# HRD_2016.net
KiCad netlist of a schematic drawn in EAGLE
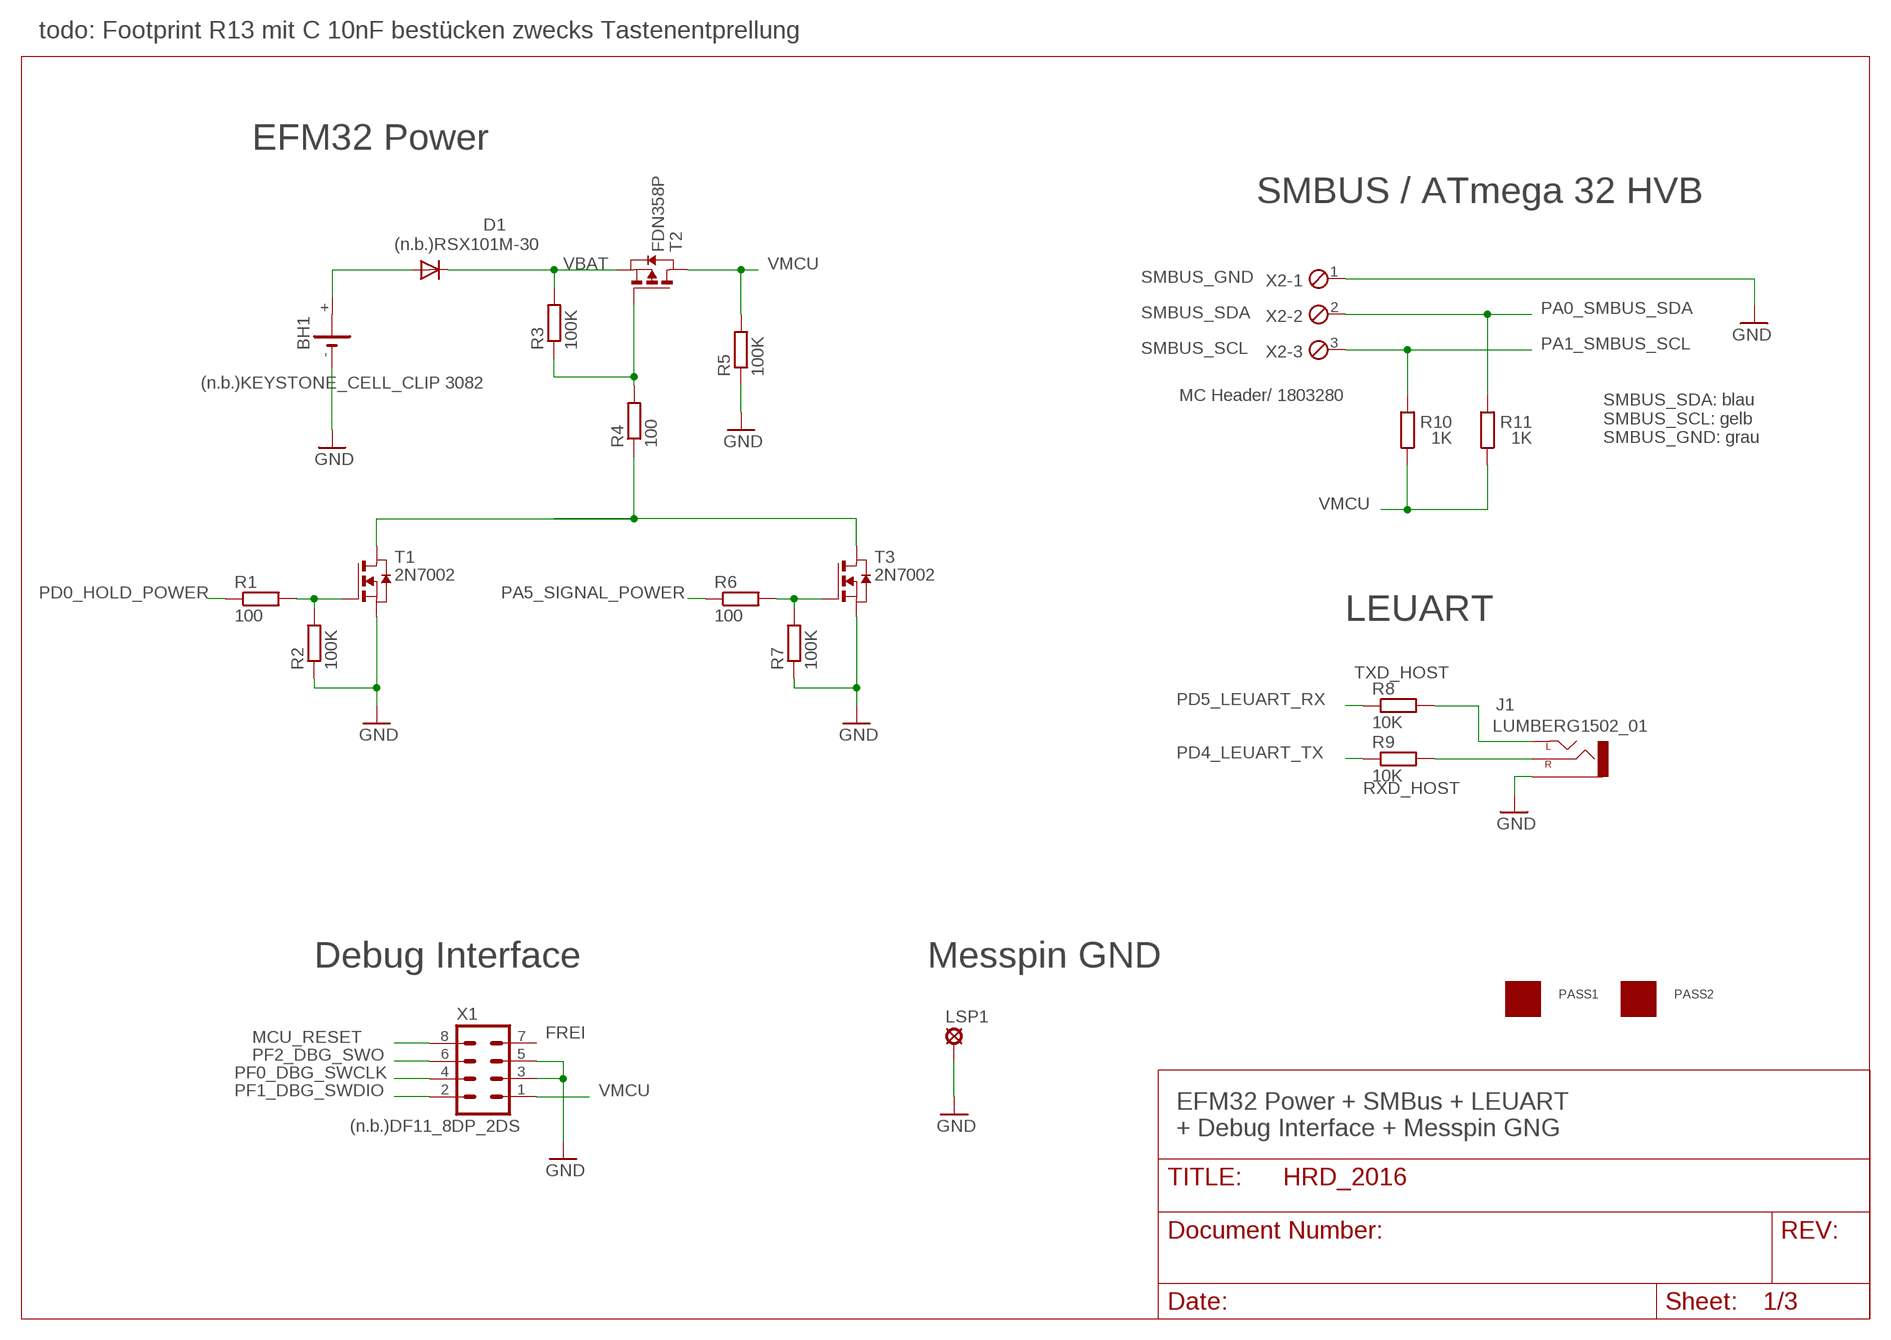
[diagram p0: schematic, sheet 1]
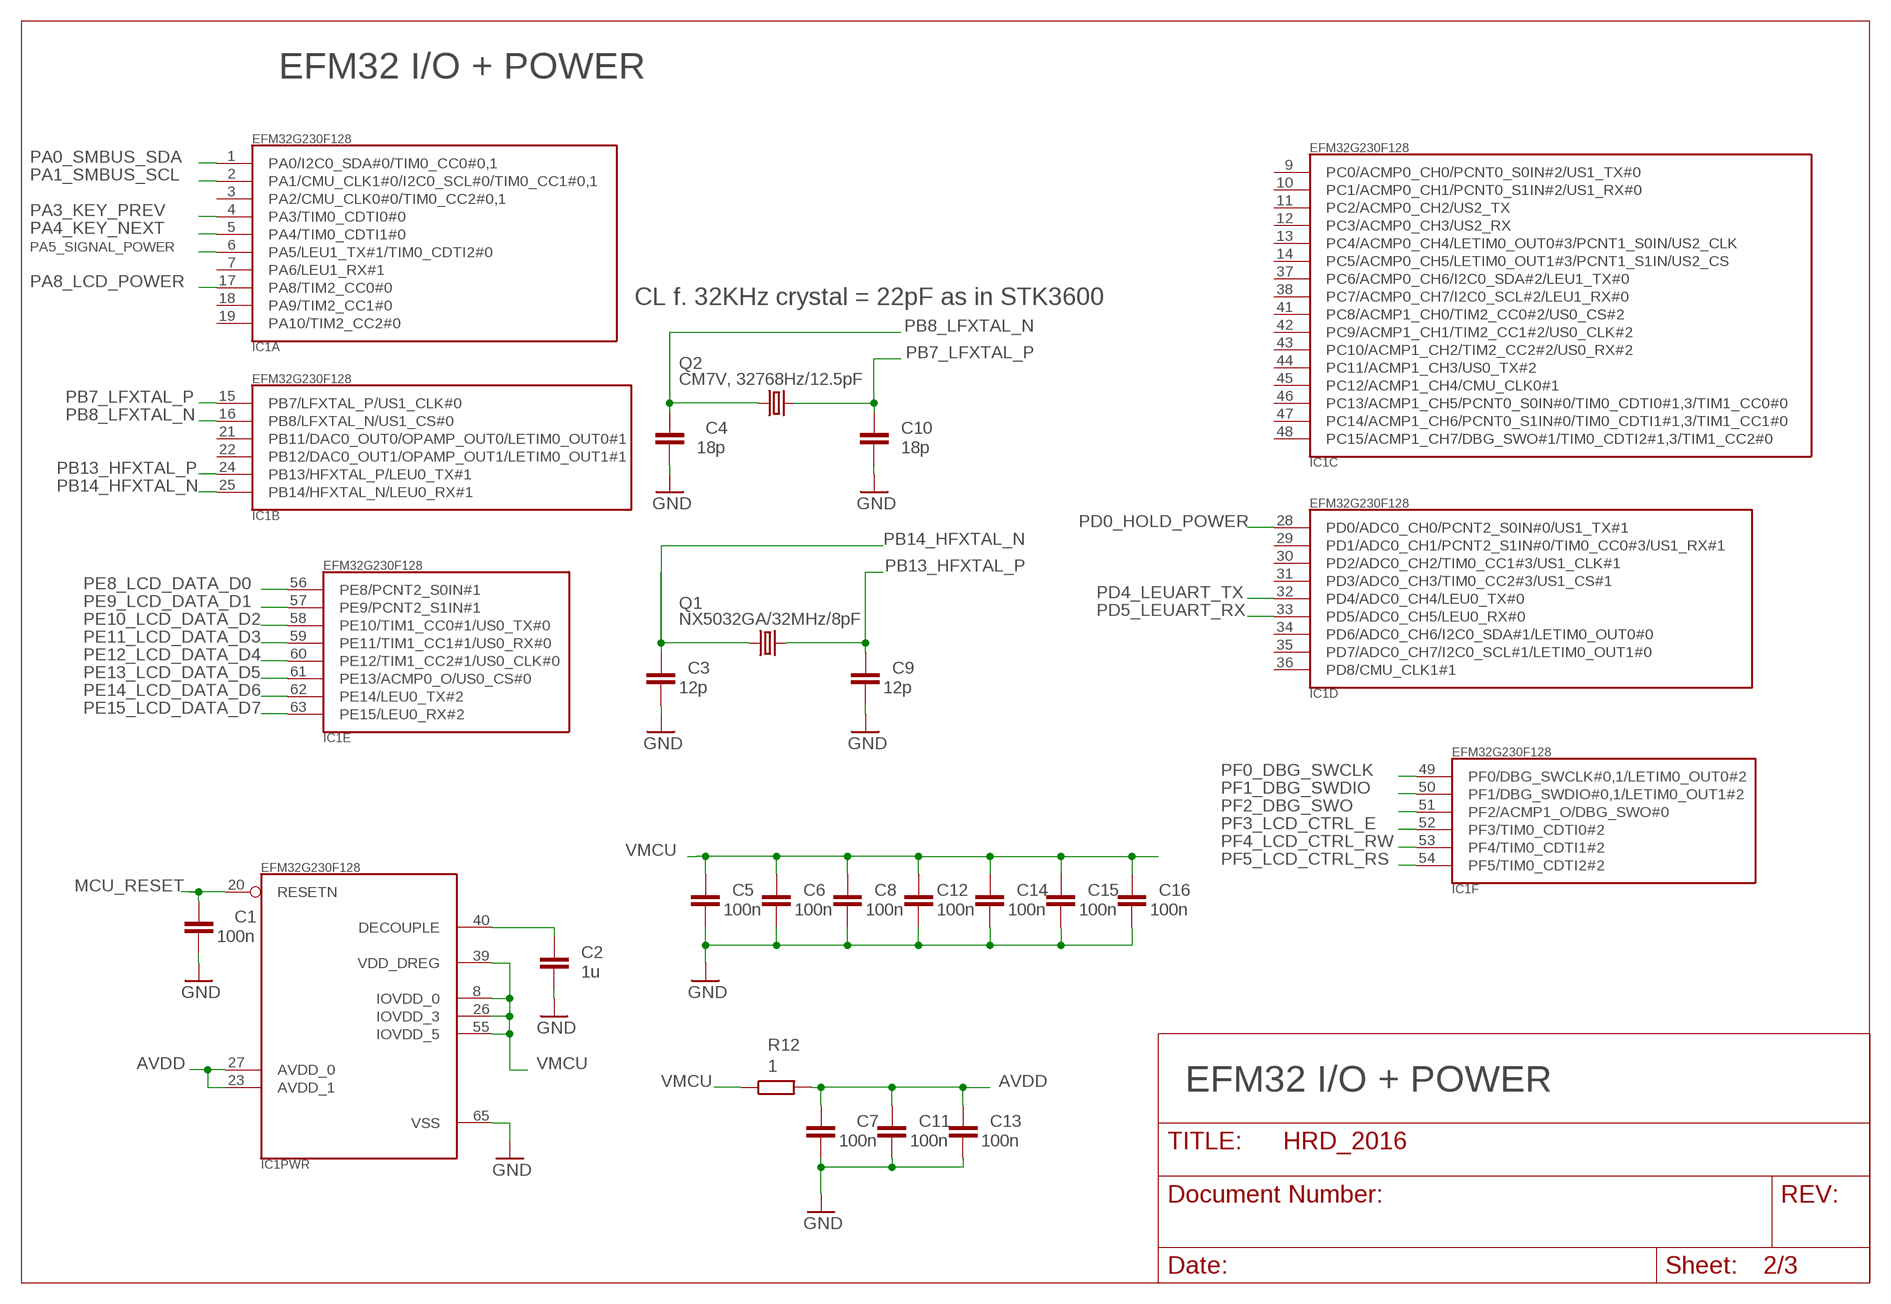
[diagram p1: schematic, sheet 2]
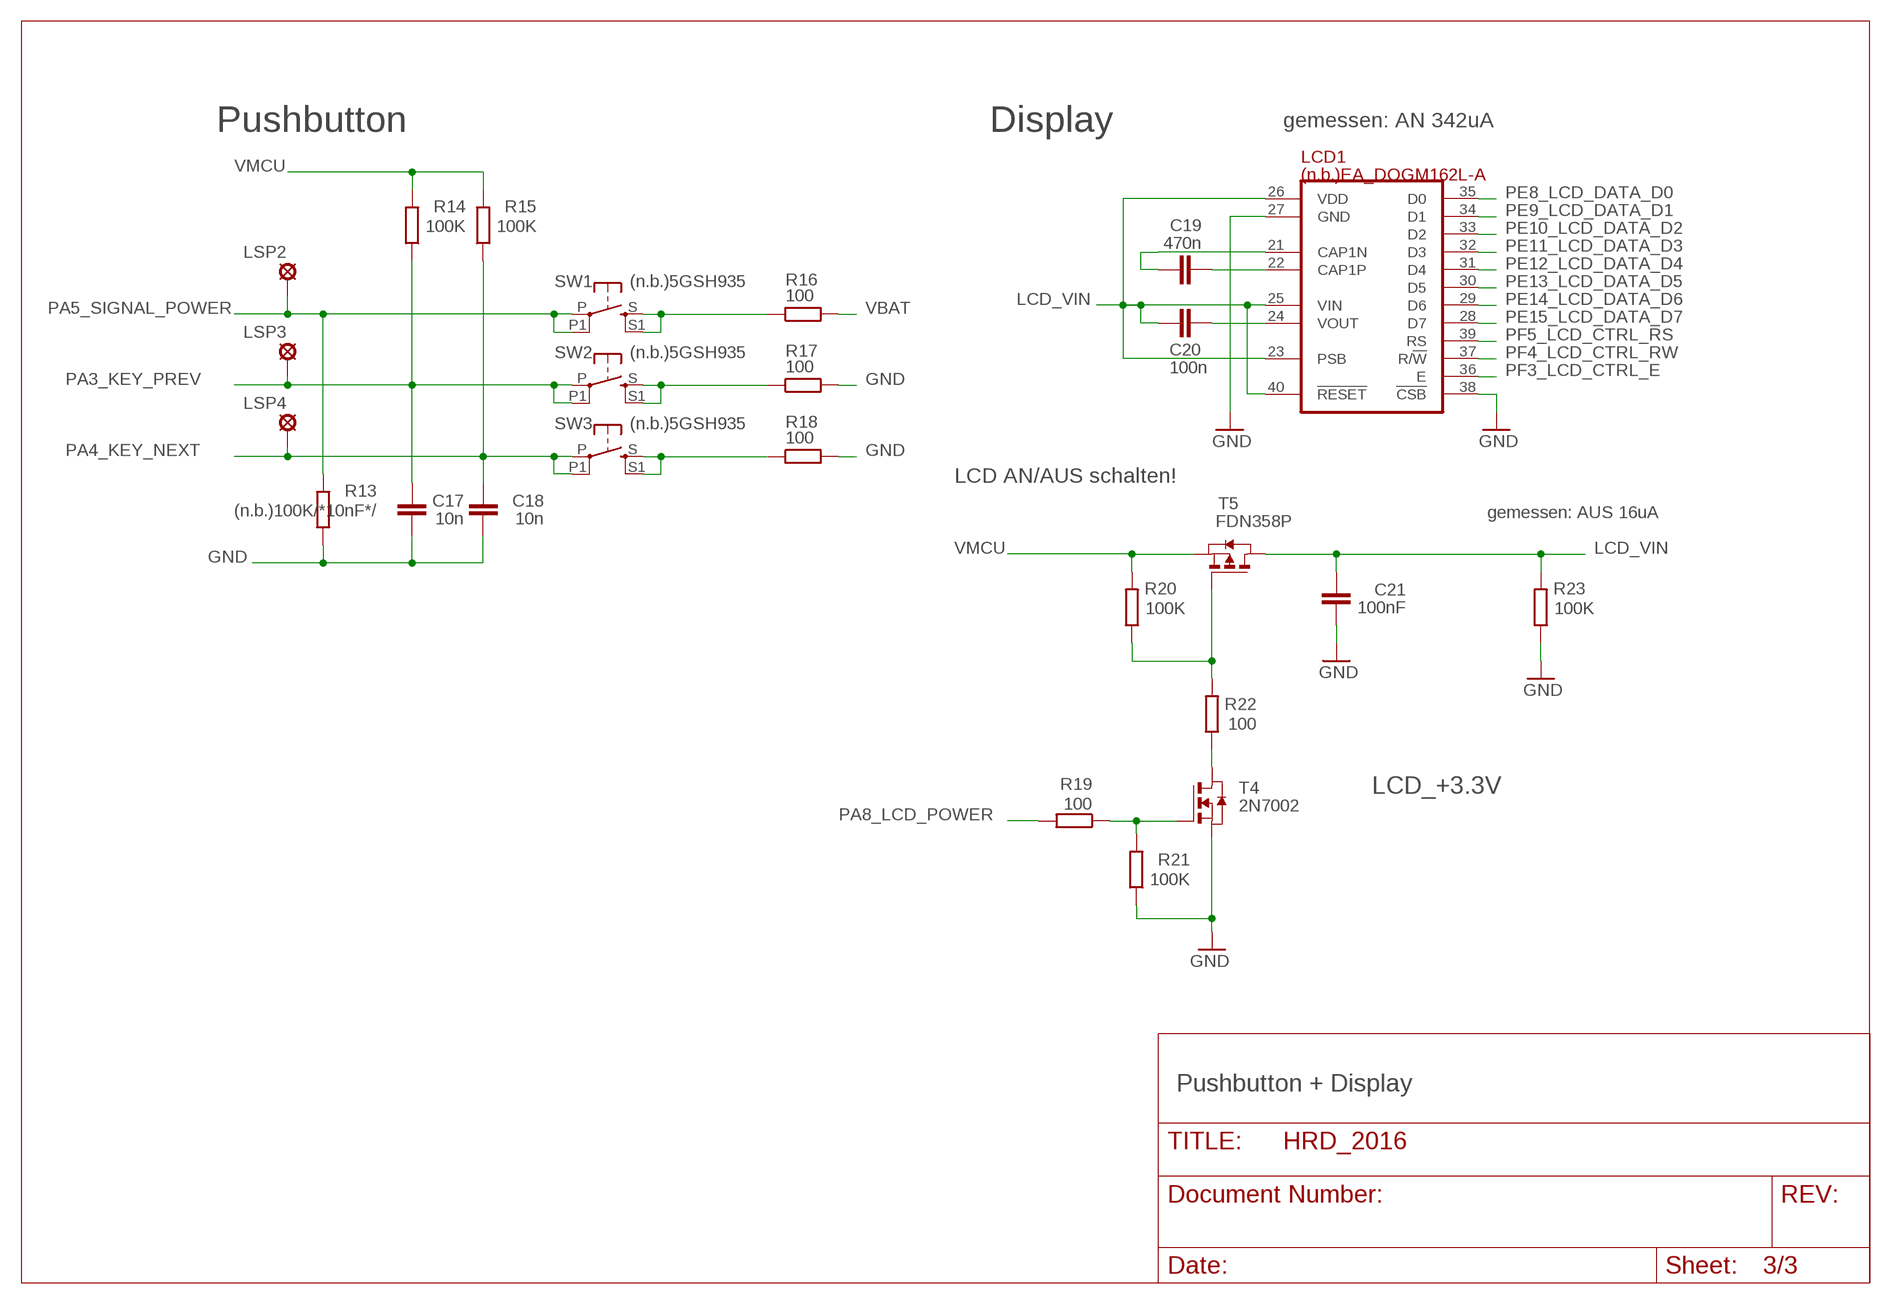
[diagram p2: schematic, sheet 3]

(export (version "E")
  (design (tool "Eeschema 10.0.6"))
  (components
    (comp (ref "C1")
      (value "100n")
      (footprint "eagle-import:C0805K")
      (libsource (lib "eagle-import") (part "C-EUC0805K"))
    )
    (comp (ref "C2")
      (value "1u")
      (footprint "eagle-import:C0805K")
      (libsource (lib "eagle-import") (part "C-EUC0805K"))
    )
    (comp (ref "C3")
      (value "12p")
      (footprint "eagle-import:C0805K")
      (libsource (lib "eagle-import") (part "C-EUC0805K"))
    )
    (comp (ref "C4")
      (value "18p")
      (footprint "eagle-import:C0805K")
      (libsource (lib "eagle-import") (part "C-EUC0805K"))
    )
    (comp (ref "C5")
      (value "100n")
      (footprint "eagle-import:C0805K")
      (libsource (lib "eagle-import") (part "C-EUC0805K"))
    )
    (comp (ref "C6")
      (value "100n")
      (footprint "eagle-import:C0805K")
      (libsource (lib "eagle-import") (part "C-EUC0805K"))
    )
    (comp (ref "C7")
      (value "100n")
      (footprint "eagle-import:C0805K")
      (libsource (lib "eagle-import") (part "C-EUC0805K"))
    )
    (comp (ref "C8")
      (value "100n")
      (footprint "eagle-import:C0805K")
      (libsource (lib "eagle-import") (part "C-EUC0805K"))
    )
    (comp (ref "C9")
      (value "12p")
      (footprint "eagle-import:C0805K")
      (libsource (lib "eagle-import") (part "C-EUC0805K"))
    )
    (comp (ref "C10")
      (value "18p")
      (footprint "eagle-import:C0805K")
      (libsource (lib "eagle-import") (part "C-EUC0805K"))
    )
    (comp (ref "C11")
      (value "100n")
      (footprint "eagle-import:C0805K")
      (libsource (lib "eagle-import") (part "C-EUC0805K"))
    )
    (comp (ref "C12")
      (value "100n")
      (footprint "eagle-import:C0805K")
      (libsource (lib "eagle-import") (part "C-EUC0805K"))
    )
    (comp (ref "C13")
      (value "100n")
      (footprint "eagle-import:C0805K")
      (libsource (lib "eagle-import") (part "C-EUC0805K"))
    )
    (comp (ref "C14")
      (value "100n")
      (footprint "eagle-import:C0805K")
      (libsource (lib "eagle-import") (part "C-EUC0805K"))
    )
    (comp (ref "C15")
      (value "100n")
      (footprint "eagle-import:C0805K")
      (libsource (lib "eagle-import") (part "C-EUC0805K"))
    )
    (comp (ref "C16")
      (value "100n")
      (footprint "eagle-import:C0805K")
      (libsource (lib "eagle-import") (part "C-EUC0805K"))
    )
    (comp (ref "IC1")
      (value "EFM32G230F128")
      (footprint "eagle-import:QFN64")
      (libsource (lib "eagle-import") (part "EFM32G230F128"))
    )
    (comp (ref "Q1")
      (value "NX5032GA/32MHz/8pF")
      (footprint "eagle-import:CRYSTAL2P5.0X3.2")
      (libsource (lib "eagle-import") (part "CRYSTAL2P5.0X3.2"))
    )
    (comp (ref "Q2")
      (value "CM7V, 32768Hz/12.5pF")
      (footprint "eagle-import:CRYSTAL2P3.2X1.5")
      (libsource (lib "eagle-import") (part "CRYSTAL2P"))
    )
    (comp (ref "R12")
      (value "1")
      (footprint "eagle-import:R0805")
      (libsource (lib "eagle-import") (part "R-EU_R0805"))
    )
    (comp (ref "BH1")
      (value "(n.b.)KEYSTONE_CELL_CLIP 3082")
      (footprint "eagle-import:3082")
      (libsource (lib "eagle-import") (part "3082"))
    )
    (comp (ref "D1")
      (value "(n.b.)RSX101M-30")
      (footprint "eagle-import:SOD123")
      (libsource (lib "eagle-import") (part "DIODE-SOD123"))
    )
    (comp (ref "J1")
      (value "LUMBERG1502_01")
      (footprint "eagle-import:LUMBERG1502_01")
      (libsource (lib "eagle-import") (part "LUMBERG1502_01"))
    )
    (comp (ref "LSP1")
      (value "(n.b.)LSP13")
      (footprint "eagle-import:LSP13")
      (libsource (lib "eagle-import") (part "LSP13"))
    )
    (comp (ref "PASS1")
      (value "ROUND_1MM1.5")
      (footprint "eagle-import:ROUND2_1.5MM")
      (libsource (lib "eagle-import") (part "ROUND_1MM1.5"))
    )
    (comp (ref "PASS2")
      (value "ROUND_1MM1.5")
      (footprint "eagle-import:ROUND2_1.5MM")
      (libsource (lib "eagle-import") (part "ROUND_1MM1.5"))
    )
    (comp (ref "R1")
      (value "100")
      (footprint "eagle-import:R0805")
      (libsource (lib "eagle-import") (part "R-EU_R0805"))
    )
    (comp (ref "R2")
      (value "100K")
      (footprint "eagle-import:R0805")
      (libsource (lib "eagle-import") (part "R-EU_R0805"))
    )
    (comp (ref "R3")
      (value "100K")
      (footprint "eagle-import:R0805")
      (libsource (lib "eagle-import") (part "R-EU_R0805"))
    )
    (comp (ref "R4")
      (value "100")
      (footprint "eagle-import:R0805")
      (libsource (lib "eagle-import") (part "R-EU_R0805"))
    )
    (comp (ref "R5")
      (value "100K")
      (footprint "eagle-import:R0805")
      (libsource (lib "eagle-import") (part "R-EU_R0805"))
    )
    (comp (ref "R6")
      (value "100")
      (footprint "eagle-import:R0805")
      (libsource (lib "eagle-import") (part "R-EU_R0805"))
    )
    (comp (ref "R7")
      (value "100K")
      (footprint "eagle-import:R0805")
      (libsource (lib "eagle-import") (part "R-EU_R0805"))
    )
    (comp (ref "R8")
      (value "10K")
      (footprint "eagle-import:R0805")
      (libsource (lib "eagle-import") (part "R-EU_R0805"))
    )
    (comp (ref "R9")
      (value "10K")
      (footprint "eagle-import:R0805")
      (libsource (lib "eagle-import") (part "R-EU_R0805"))
    )
    (comp (ref "R10")
      (value "1K")
      (footprint "eagle-import:R0805")
      (libsource (lib "eagle-import") (part "resistor_R-EU_R0805"))
    )
    (comp (ref "R11")
      (value "1K")
      (footprint "eagle-import:R0805")
      (libsource (lib "eagle-import") (part "resistor_R-EU_R0805"))
    )
    (comp (ref "T1")
      (value "2N7002")
      (footprint "eagle-import:SOT-23")
      (fields (field (name "OC_FARNELL") "unknown") (field (name "OC_NEWARK") "unknown"))
      (libsource (lib "eagle-import") (part "NMOSSOT23"))
    )
    (comp (ref "T2")
      (value "FDN358P")
      (footprint "eagle-import:ZETEX_SOT-23")
      (libsource (lib "eagle-import") (part "ZETEX_PMOSSOT23"))
    )
    (comp (ref "T3")
      (value "2N7002")
      (footprint "eagle-import:SOT-23")
      (fields (field (name "OC_FARNELL") "unknown") (field (name "OC_NEWARK") "unknown"))
      (libsource (lib "eagle-import") (part "NMOSSOT23"))
    )
    (comp (ref "X1")
      (value "(n.b.)DF11_8DP_2DS")
      (footprint "eagle-import:DP11_8DP-2DS")
      (libsource (lib "eagle-import") (part "DP11_8DP_2DS"))
    )
    (comp (ref "X2")
      (value "MC Header/ 1803280")
      (footprint "eagle-import:3POL381")
      (libsource (lib "eagle-import") (part "MKDS1/3-3,81"))
    )
    (comp (ref "C17")
      (value "10n")
      (footprint "eagle-import:C0603K")
      (libsource (lib "eagle-import") (part "C-EUC0603K"))
    )
    (comp (ref "C18")
      (value "10n")
      (footprint "eagle-import:C0603K")
      (libsource (lib "eagle-import") (part "C-EUC0603K"))
    )
    (comp (ref "C19")
      (value "470n")
      (footprint "eagle-import:C0603K")
      (libsource (lib "eagle-import") (part "C-EUC0603K"))
    )
    (comp (ref "C20")
      (value "100n")
      (footprint "eagle-import:C0603K")
      (libsource (lib "eagle-import") (part "C-EUC0603K"))
    )
    (comp (ref "C21")
      (value "100nF")
      (footprint "eagle-import:C0603K")
      (libsource (lib "eagle-import") (part "C-EUC0603K"))
    )
    (comp (ref "LCD1")
      (value "(n.b.)EA_DOGM162L-A")
      (footprint "eagle-import:EA_DOGM")
      (libsource (lib "eagle-import") (part "EA_DOGM162"))
    )
    (comp (ref "LSP2")
      (value "(n.b.)SE13")
      (footprint "eagle-import:SE13")
      (libsource (lib "eagle-import") (part "SE13"))
    )
    (comp (ref "LSP3")
      (value "(n.b.)SE13")
      (footprint "eagle-import:SE13")
      (libsource (lib "eagle-import") (part "SE13"))
    )
    (comp (ref "LSP4")
      (value "(n.b.)SE13")
      (footprint "eagle-import:SE13")
      (libsource (lib "eagle-import") (part "SE13"))
    )
    (comp (ref "R13")
      (value "(n.b.)100K/*10nF*/")
      (footprint "eagle-import:R0805")
      (libsource (lib "eagle-import") (part "resistor_R-EU_R0805"))
    )
    (comp (ref "R14")
      (value "100K")
      (footprint "eagle-import:R0805")
      (libsource (lib "eagle-import") (part "resistor_R-EU_R0805"))
    )
    (comp (ref "R15")
      (value "100K")
      (footprint "eagle-import:R0805")
      (libsource (lib "eagle-import") (part "resistor_R-EU_R0805"))
    )
    (comp (ref "R16")
      (value "100")
      (footprint "eagle-import:R0805")
      (libsource (lib "eagle-import") (part "resistor_R-EU_R0805"))
    )
    (comp (ref "R17")
      (value "100")
      (footprint "eagle-import:R0805")
      (libsource (lib "eagle-import") (part "resistor_R-EU_R0805"))
    )
    (comp (ref "R18")
      (value "100")
      (footprint "eagle-import:R0805")
      (libsource (lib "eagle-import") (part "resistor_R-EU_R0805"))
    )
    (comp (ref "R19")
      (value "100")
      (footprint "eagle-import:R0805")
      (libsource (lib "eagle-import") (part "resistor_R-EU_R0805"))
    )
    (comp (ref "R20")
      (value "100K")
      (footprint "eagle-import:R0805")
      (libsource (lib "eagle-import") (part "resistor_R-EU_R0805"))
    )
    (comp (ref "R21")
      (value "100K")
      (footprint "eagle-import:R0805")
      (libsource (lib "eagle-import") (part "resistor_R-EU_R0805"))
    )
    (comp (ref "R22")
      (value "100")
      (footprint "eagle-import:R0805")
      (libsource (lib "eagle-import") (part "resistor_R-EU_R0805"))
    )
    (comp (ref "R23")
      (value "100K")
      (footprint "eagle-import:R0805")
      (libsource (lib "eagle-import") (part "resistor_R-EU_R0805"))
    )
    (comp (ref "SW1")
      (value "(n.b.)5GSH935")
      (footprint "eagle-import:MULTIMEC_5GSH935")
      (libsource (lib "eagle-import") (part "5GSH935"))
    )
    (comp (ref "SW2")
      (value "(n.b.)5GSH935")
      (footprint "eagle-import:MULTIMEC_5GSH935")
      (libsource (lib "eagle-import") (part "5GSH935"))
    )
    (comp (ref "SW3")
      (value "(n.b.)5GSH935")
      (footprint "eagle-import:MULTIMEC_5GSH935")
      (libsource (lib "eagle-import") (part "5GSH935"))
    )
    (comp (ref "T4")
      (value "2N7002")
      (footprint "eagle-import:ZETEX_SOT-23")
      (libsource (lib "eagle-import") (part "ZETEX_NMOSSOT23"))
    )
    (comp (ref "T5")
      (value "FDN358P")
      (footprint "eagle-import:ZETEX_SOT-23")
      (libsource (lib "eagle-import") (part "ZETEX_PMOSSOT23"))
    )
  )
  (nets
    (net (code "1") (name "AVDD") (class "Default")
      (node (ref "C11") (pin "2") (pinfunction "2_2") (pintype "passive"))
      (node (ref "C13") (pin "2") (pinfunction "2_2") (pintype "passive"))
      (node (ref "C7") (pin "2") (pinfunction "2_2") (pintype "passive"))
      (node (ref "IC1") (pin "23") (pinfunction "AVDD_1_23") (pintype "power_in"))
      (node (ref "IC1") (pin "27") (pinfunction "AVDD_0_27") (pintype "power_in"))
      (node (ref "R12") (pin "2") (pinfunction "2_2") (pintype "passive"))
    )
    (net (code "2") (name "GND") (class "Default")
      (node (ref "BH1") (pin "-") (pinfunction "-_-") (pintype "passive"))
      (node (ref "C1") (pin "1") (pinfunction "1_1") (pintype "passive"))
      (node (ref "C10") (pin "1") (pinfunction "1_1") (pintype "passive"))
      (node (ref "C11") (pin "1") (pinfunction "1_1") (pintype "passive"))
      (node (ref "C12") (pin "1") (pinfunction "1_1") (pintype "passive"))
      (node (ref "C13") (pin "1") (pinfunction "1_1") (pintype "passive"))
      (node (ref "C14") (pin "1") (pinfunction "1_1") (pintype "passive"))
      (node (ref "C15") (pin "1") (pinfunction "1_1") (pintype "passive"))
      (node (ref "C16") (pin "1") (pinfunction "1_1") (pintype "passive"))
      (node (ref "C17") (pin "1") (pinfunction "1_1") (pintype "passive"))
      (node (ref "C18") (pin "1") (pinfunction "1_1") (pintype "passive"))
      (node (ref "C2") (pin "1") (pinfunction "1_1") (pintype "passive"))
      (node (ref "C21") (pin "2") (pinfunction "2_2") (pintype "passive"))
      (node (ref "C3") (pin "1") (pinfunction "1_1") (pintype "passive"))
      (node (ref "C4") (pin "1") (pinfunction "1_1") (pintype "passive"))
      (node (ref "C5") (pin "1") (pinfunction "1_1") (pintype "passive"))
      (node (ref "C6") (pin "1") (pinfunction "1_1") (pintype "passive"))
      (node (ref "C7") (pin "1") (pinfunction "1_1") (pintype "passive"))
      (node (ref "C8") (pin "1") (pinfunction "1_1") (pintype "passive"))
      (node (ref "C9") (pin "1") (pinfunction "1_1") (pintype "passive"))
      (node (ref "IC1") (pin "65") (pinfunction "VSS_65") (pintype "power_in"))
      (node (ref "J1") (pin "P$1") (pinfunction "1-SLEEVE_P$1") (pintype "bidirectional"))
      (node (ref "LCD1") (pin "27") (pinfunction "GND_27") (pintype "power_in"))
      (node (ref "LCD1") (pin "38") (pinfunction "~{CSB}_38") (pintype "input"))
      (node (ref "LSP1") (pin "MP") (pinfunction "MP_MP") (pintype "passive"))
      (node (ref "R13") (pin "1") (pinfunction "1_1") (pintype "passive"))
      (node (ref "R17") (pin "2") (pinfunction "2_2") (pintype "passive"))
      (node (ref "R18") (pin "2") (pinfunction "2_2") (pintype "passive"))
      (node (ref "R2") (pin "1") (pinfunction "1_1") (pintype "passive"))
      (node (ref "R21") (pin "1") (pinfunction "1_1") (pintype "passive"))
      (node (ref "R23") (pin "1") (pinfunction "1_1") (pintype "passive"))
      (node (ref "R5") (pin "1") (pinfunction "1_1") (pintype "passive"))
      (node (ref "R7") (pin "1") (pinfunction "1_1") (pintype "passive"))
      (node (ref "T1") (pin "2") (pinfunction "S_2") (pintype "passive"))
      (node (ref "T3") (pin "2") (pinfunction "S_2") (pintype "passive"))
      (node (ref "T4") (pin "2") (pinfunction "S_2") (pintype "passive"))
      (node (ref "X1") (pin "3") (pinfunction "3_3") (pintype "passive"))
      (node (ref "X1") (pin "5") (pinfunction "5_5") (pintype "passive"))
      (node (ref "X2") (pin "1") (pinfunction "1_1") (pintype "passive"))
    )
    (net (code "3") (name "LCD_VIN") (class "Default")
      (node (ref "C20") (pin "2") (pinfunction "2_2") (pintype "passive"))
      (node (ref "C21") (pin "1") (pinfunction "1_1") (pintype "passive"))
      (node (ref "LCD1") (pin "23") (pinfunction "PSB_23") (pintype "input"))
      (node (ref "LCD1") (pin "25") (pinfunction "VIN_25") (pintype "passive"))
      (node (ref "LCD1") (pin "26") (pinfunction "VDD_26") (pintype "power_in"))
      (node (ref "LCD1") (pin "40") (pinfunction "~{RESET}_40") (pintype "input"))
      (node (ref "R23") (pin "2") (pinfunction "2_2") (pintype "passive"))
      (node (ref "T5") (pin "1") (pinfunction "D_1") (pintype "passive"))
    )
    (net (code "4") (name "MCU_RESET") (class "Default")
      (node (ref "C1") (pin "2") (pinfunction "2_2") (pintype "passive"))
      (node (ref "IC1") (pin "20") (pinfunction "RESETN_20") (pintype "passive"))
      (node (ref "X1") (pin "8") (pinfunction "8_8") (pintype "passive"))
    )
    (net (code "5") (name "Net-(BH1-Pad+)") (class "Default")
      (node (ref "BH1") (pin "+") (pinfunction "+_+") (pintype "passive"))
      (node (ref "D1") (pin "A") (pinfunction "A_A") (pintype "passive"))
    )
    (net (code "6") (name "Net-(IC1G-DECOUPLE)") (class "Default")
      (node (ref "C2") (pin "2") (pinfunction "2_2") (pintype "passive"))
      (node (ref "IC1") (pin "40") (pinfunction "DECOUPLE_40") (pintype "power_in"))
    )
    (net (code "7") (name "Net-(LCD1-CAP1N)") (class "Default")
      (node (ref "C19") (pin "1") (pinfunction "1_1") (pintype "passive"))
      (node (ref "LCD1") (pin "21") (pinfunction "CAP1N_21") (pintype "passive"))
    )
    (net (code "8") (name "Net-(LCD1-CAP1P)") (class "Default")
      (node (ref "C19") (pin "2") (pinfunction "2_2") (pintype "passive"))
      (node (ref "LCD1") (pin "22") (pinfunction "CAP1P_22") (pintype "passive"))
    )
    (net (code "9") (name "Net-(LCD1-VOUT)") (class "Default")
      (node (ref "C20") (pin "1") (pinfunction "1_1") (pintype "passive"))
      (node (ref "LCD1") (pin "24") (pinfunction "VOUT_24") (pintype "passive"))
    )
    (net (code "10") (name "Net-(R16-Pad1)") (class "Default")
      (node (ref "R16") (pin "1") (pinfunction "1_1") (pintype "passive"))
      (node (ref "SW1") (pin "S") (pinfunction "S_S") (pintype "passive"))
      (node (ref "SW1") (pin "S1") (pinfunction "S1_S1") (pintype "passive"))
    )
    (net (code "11") (name "Net-(R17-Pad1)") (class "Default")
      (node (ref "R17") (pin "1") (pinfunction "1_1") (pintype "passive"))
      (node (ref "SW2") (pin "S") (pinfunction "S_S") (pintype "passive"))
      (node (ref "SW2") (pin "S1") (pinfunction "S1_S1") (pintype "passive"))
    )
    (net (code "12") (name "Net-(R18-Pad1)") (class "Default")
      (node (ref "R18") (pin "1") (pinfunction "1_1") (pintype "passive"))
      (node (ref "SW3") (pin "S") (pinfunction "S_S") (pintype "passive"))
      (node (ref "SW3") (pin "S1") (pinfunction "S1_S1") (pintype "passive"))
    )
    (net (code "13") (name "Net-(T1-D)") (class "Default")
      (node (ref "R4") (pin "1") (pinfunction "1_1") (pintype "passive"))
      (node (ref "T1") (pin "1") (pinfunction "D_1") (pintype "passive"))
      (node (ref "T3") (pin "1") (pinfunction "D_1") (pintype "passive"))
    )
    (net (code "14") (name "Net-(T1-G)") (class "Default")
      (node (ref "R1") (pin "2") (pinfunction "2_2") (pintype "passive"))
      (node (ref "R2") (pin "2") (pinfunction "2_2") (pintype "passive"))
      (node (ref "T1") (pin "3") (pinfunction "G_3") (pintype "passive"))
    )
    (net (code "15") (name "Net-(T2-G)") (class "Default")
      (node (ref "R3") (pin "1") (pinfunction "1_1") (pintype "passive"))
      (node (ref "R4") (pin "2") (pinfunction "2_2") (pintype "passive"))
      (node (ref "T2") (pin "3") (pinfunction "G_3") (pintype "passive"))
    )
    (net (code "16") (name "Net-(T3-G)") (class "Default")
      (node (ref "R6") (pin "2") (pinfunction "2_2") (pintype "passive"))
      (node (ref "R7") (pin "2") (pinfunction "2_2") (pintype "passive"))
      (node (ref "T3") (pin "3") (pinfunction "G_3") (pintype "passive"))
    )
    (net (code "17") (name "Net-(T4-D)") (class "Default")
      (node (ref "R22") (pin "1") (pinfunction "1_1") (pintype "passive"))
      (node (ref "T4") (pin "1") (pinfunction "D_1") (pintype "passive"))
    )
    (net (code "18") (name "Net-(T4-G)") (class "Default")
      (node (ref "R19") (pin "1") (pinfunction "1_1") (pintype "passive"))
      (node (ref "R21") (pin "2") (pinfunction "2_2") (pintype "passive"))
      (node (ref "T4") (pin "3") (pinfunction "G_3") (pintype "passive"))
    )
    (net (code "19") (name "Net-(T5-G)") (class "Default")
      (node (ref "R20") (pin "1") (pinfunction "1_1") (pintype "passive"))
      (node (ref "R22") (pin "2") (pinfunction "2_2") (pintype "passive"))
      (node (ref "T5") (pin "3") (pinfunction "G_3") (pintype "passive"))
    )
    (net (code "20") (name "PA0_SMBUS_SDA") (class "Default")
      (node (ref "IC1") (pin "1") (pinfunction "PA0/I2C0_SDA#0/TIM0_CC0#0,1_1") (pintype "bidirectional"))
      (node (ref "R11") (pin "2") (pinfunction "2_2") (pintype "passive"))
      (node (ref "X2") (pin "2") (pinfunction "1_2") (pintype "passive"))
    )
    (net (code "21") (name "PA1_SMBUS_SCL") (class "Default")
      (node (ref "IC1") (pin "2") (pinfunction "PA1/CMU_CLK1#0/I2C0_SCL#0/TIM0_CC1#0,1_2") (pintype "bidirectional"))
      (node (ref "R10") (pin "2") (pinfunction "2_2") (pintype "passive"))
      (node (ref "X2") (pin "3") (pinfunction "1_3") (pintype "passive"))
    )
    (net (code "22") (name "PA3_KEY_PREV") (class "Default")
      (node (ref "C17") (pin "2") (pinfunction "2_2") (pintype "passive"))
      (node (ref "IC1") (pin "4") (pinfunction "PA3/TIM0_CDTI0#0_4") (pintype "bidirectional"))
      (node (ref "LSP3") (pin "MP") (pinfunction "MP_MP") (pintype "passive"))
      (node (ref "R14") (pin "1") (pinfunction "1_1") (pintype "passive"))
      (node (ref "SW2") (pin "P") (pinfunction "P_P") (pintype "passive"))
      (node (ref "SW2") (pin "P1") (pinfunction "P1_P1") (pintype "passive"))
    )
    (net (code "23") (name "PA4_KEY_NEXT") (class "Default")
      (node (ref "C18") (pin "2") (pinfunction "2_2") (pintype "passive"))
      (node (ref "IC1") (pin "5") (pinfunction "PA4/TIM0_CDTI1#0_5") (pintype "bidirectional"))
      (node (ref "LSP4") (pin "MP") (pinfunction "MP_MP") (pintype "passive"))
      (node (ref "R15") (pin "1") (pinfunction "1_1") (pintype "passive"))
      (node (ref "SW3") (pin "P") (pinfunction "P_P") (pintype "passive"))
      (node (ref "SW3") (pin "P1") (pinfunction "P1_P1") (pintype "passive"))
    )
    (net (code "24") (name "PA5_SIGNAL_POWER") (class "Default")
      (node (ref "IC1") (pin "6") (pinfunction "PA5/LEU1_TX#1/TIM0_CDTI2#0_6") (pintype "bidirectional"))
      (node (ref "LSP2") (pin "MP") (pinfunction "MP_MP") (pintype "passive"))
      (node (ref "R13") (pin "2") (pinfunction "2_2") (pintype "passive"))
      (node (ref "R6") (pin "1") (pinfunction "1_1") (pintype "passive"))
      (node (ref "SW1") (pin "P") (pinfunction "P_P") (pintype "passive"))
      (node (ref "SW1") (pin "P1") (pinfunction "P1_P1") (pintype "passive"))
    )
    (net (code "25") (name "PA8_LCD_POWER") (class "Default")
      (node (ref "IC1") (pin "17") (pinfunction "PA8/TIM2_CC0#0_17") (pintype "bidirectional"))
      (node (ref "R19") (pin "2") (pinfunction "2_2") (pintype "passive"))
    )
    (net (code "26") (name "PB7_LFXTAL_P") (class "Default")
      (node (ref "C10") (pin "2") (pinfunction "2_2") (pintype "passive"))
      (node (ref "IC1") (pin "15") (pinfunction "PB7/LFXTAL_P/US1_CLK#0_15") (pintype "bidirectional"))
      (node (ref "Q2") (pin "2") (pinfunction "2_2") (pintype "passive"))
    )
    (net (code "27") (name "PB8_LFXTAL_N") (class "Default")
      (node (ref "C4") (pin "2") (pinfunction "2_2") (pintype "passive"))
      (node (ref "IC1") (pin "16") (pinfunction "PB8/LFXTAL_N/US1_CS#0_16") (pintype "bidirectional"))
      (node (ref "Q2") (pin "1") (pinfunction "1_1") (pintype "passive"))
    )
    (net (code "28") (name "PB13_HFXTAL_P") (class "Default")
      (node (ref "C9") (pin "2") (pinfunction "2_2") (pintype "passive"))
      (node (ref "IC1") (pin "24") (pinfunction "PB13/HFXTAL_P/LEU0_TX#1_24") (pintype "bidirectional"))
      (node (ref "Q1") (pin "2") (pinfunction "2_2") (pintype "passive"))
    )
    (net (code "29") (name "PB14_HFXTAL_N") (class "Default")
      (node (ref "C3") (pin "2") (pinfunction "2_2") (pintype "passive"))
      (node (ref "IC1") (pin "25") (pinfunction "PB14/HFXTAL_N/LEU0_RX#1_25") (pintype "bidirectional"))
      (node (ref "Q1") (pin "1") (pinfunction "1_1") (pintype "passive"))
    )
    (net (code "30") (name "PD0_HOLD_POWER") (class "Default")
      (node (ref "IC1") (pin "28") (pinfunction "PD0/ADC0_CH0/PCNT2_S0IN#0/US1_TX#1_28") (pintype "bidirectional"))
      (node (ref "R1") (pin "1") (pinfunction "1_1") (pintype "passive"))
    )
    (net (code "31") (name "PD4_LEUART_TX") (class "Default")
      (node (ref "IC1") (pin "32") (pinfunction "PD4/ADC0_CH4/LEU0_TX#0_32") (pintype "bidirectional"))
      (node (ref "R9") (pin "1") (pinfunction "1_1") (pintype "passive"))
    )
    (net (code "32") (name "PD5_LEUART_RX") (class "Default")
      (node (ref "IC1") (pin "33") (pinfunction "PD5/ADC0_CH5/LEU0_RX#0_33") (pintype "bidirectional"))
      (node (ref "R8") (pin "1") (pinfunction "1_1") (pintype "passive"))
    )
    (net (code "33") (name "PE8_LCD_DATA_D0") (class "Default")
      (node (ref "IC1") (pin "56") (pinfunction "PE8/PCNT2_S0IN#1_56") (pintype "bidirectional"))
      (node (ref "LCD1") (pin "35") (pinfunction "D0_35") (pintype "bidirectional"))
    )
    (net (code "34") (name "PE9_LCD_DATA_D1") (class "Default")
      (node (ref "IC1") (pin "57") (pinfunction "PE9/PCNT2_S1IN#1_57") (pintype "bidirectional"))
      (node (ref "LCD1") (pin "34") (pinfunction "D1_34") (pintype "bidirectional"))
    )
    (net (code "35") (name "PE10_LCD_DATA_D2") (class "Default")
      (node (ref "IC1") (pin "58") (pinfunction "PE10/TIM1_CC0#1/US0_TX#0_58") (pintype "bidirectional"))
      (node (ref "LCD1") (pin "33") (pinfunction "D2_33") (pintype "bidirectional"))
    )
    (net (code "36") (name "PE11_LCD_DATA_D3") (class "Default")
      (node (ref "IC1") (pin "59") (pinfunction "PE11/TIM1_CC1#1/US0_RX#0_59") (pintype "bidirectional"))
      (node (ref "LCD1") (pin "32") (pinfunction "D3_32") (pintype "bidirectional"))
    )
    (net (code "37") (name "PE12_LCD_DATA_D4") (class "Default")
      (node (ref "IC1") (pin "60") (pinfunction "PE12/TIM1_CC2#1/US0_CLK#0_60") (pintype "bidirectional"))
      (node (ref "LCD1") (pin "31") (pinfunction "D4_31") (pintype "bidirectional"))
    )
    (net (code "38") (name "PE13_LCD_DATA_D5") (class "Default")
      (node (ref "IC1") (pin "61") (pinfunction "PE13/ACMP0_O/US0_CS#0_61") (pintype "bidirectional"))
      (node (ref "LCD1") (pin "30") (pinfunction "D5_30") (pintype "bidirectional"))
    )
    (net (code "39") (name "PE14_LCD_DATA_D6") (class "Default")
      (node (ref "IC1") (pin "62") (pinfunction "PE14/LEU0_TX#2_62") (pintype "bidirectional"))
      (node (ref "LCD1") (pin "29") (pinfunction "D6_29") (pintype "bidirectional"))
    )
    (net (code "40") (name "PE15_LCD_DATA_D7") (class "Default")
      (node (ref "IC1") (pin "63") (pinfunction "PE15/LEU0_RX#2_63") (pintype "bidirectional"))
      (node (ref "LCD1") (pin "28") (pinfunction "D7_28") (pintype "bidirectional"))
    )
    (net (code "41") (name "PF0_DBG_SWCLK") (class "Default")
      (node (ref "IC1") (pin "49") (pinfunction "PF0/DBG_SWCLK#0,1/LETIM0_OUT0#2_49") (pintype "bidirectional"))
      (node (ref "X1") (pin "4") (pinfunction "4_4") (pintype "passive"))
    )
    (net (code "42") (name "PF1_DBG_SWDIO") (class "Default")
      (node (ref "IC1") (pin "50") (pinfunction "PF1/DBG_SWDIO#0,1/LETIM0_OUT1#2_50") (pintype "bidirectional"))
      (node (ref "X1") (pin "2") (pinfunction "2_2") (pintype "passive"))
    )
    (net (code "43") (name "PF2_DBG_SWO") (class "Default")
      (node (ref "IC1") (pin "51") (pinfunction "PF2/ACMP1_O/DBG_SWO#0_51") (pintype "bidirectional"))
      (node (ref "X1") (pin "6") (pinfunction "6_6") (pintype "passive"))
    )
    (net (code "44") (name "PF3_LCD_CTRL_E") (class "Default")
      (node (ref "IC1") (pin "52") (pinfunction "PF3/TIM0_CDTI0#2_52") (pintype "bidirectional"))
      (node (ref "LCD1") (pin "36") (pinfunction "E_36") (pintype "input"))
    )
    (net (code "45") (name "PF4_LCD_CTRL_RW") (class "Default")
      (node (ref "IC1") (pin "53") (pinfunction "PF4/TIM0_CDTI1#2_53") (pintype "bidirectional"))
      (node (ref "LCD1") (pin "37") (pinfunction "R/~{W}_37") (pintype "input"))
    )
    (net (code "46") (name "PF5_LCD_CTRL_RS") (class "Default")
      (node (ref "IC1") (pin "54") (pinfunction "PF5/TIM0_CDTI2#2_54") (pintype "bidirectional"))
      (node (ref "LCD1") (pin "39") (pinfunction "RS_39") (pintype "input"))
    )
    (net (code "47") (name "RXD_HOST") (class "Default")
      (node (ref "J1") (pin "P$3") (pinfunction "3-RIGHT_P$3") (pintype "bidirectional"))
      (node (ref "R9") (pin "2") (pinfunction "2_2") (pintype "passive"))
    )
    (net (code "48") (name "TXD_HOST") (class "Default")
      (node (ref "J1") (pin "P$2") (pinfunction "2-LEFT_P$2") (pintype "bidirectional"))
      (node (ref "R8") (pin "2") (pinfunction "2_2") (pintype "passive"))
    )
    (net (code "49") (name "VBAT") (class "Default")
      (node (ref "D1") (pin "C") (pinfunction "C_C") (pintype "passive"))
      (node (ref "R16") (pin "2") (pinfunction "2_2") (pintype "passive"))
      (node (ref "R3") (pin "2") (pinfunction "2_2") (pintype "passive"))
      (node (ref "T2") (pin "2") (pinfunction "S_2") (pintype "passive"))
    )
    (net (code "50") (name "VMCU") (class "Default")
      (node (ref "C12") (pin "2") (pinfunction "2_2") (pintype "passive"))
      (node (ref "C14") (pin "2") (pinfunction "2_2") (pintype "passive"))
      (node (ref "C15") (pin "2") (pinfunction "2_2") (pintype "passive"))
      (node (ref "C16") (pin "2") (pinfunction "2_2") (pintype "passive"))
      (node (ref "C5") (pin "2") (pinfunction "2_2") (pintype "passive"))
      (node (ref "C6") (pin "2") (pinfunction "2_2") (pintype "passive"))
      (node (ref "C8") (pin "2") (pinfunction "2_2") (pintype "passive"))
      (node (ref "IC1") (pin "26") (pinfunction "IOVDD_3_26") (pintype "power_in"))
      (node (ref "IC1") (pin "39") (pinfunction "VDD_DREG_39") (pintype "power_in"))
      (node (ref "IC1") (pin "55") (pinfunction "IOVDD_5_55") (pintype "power_in"))
      (node (ref "IC1") (pin "8") (pinfunction "IOVDD_0_8") (pintype "power_in"))
      (node (ref "R10") (pin "1") (pinfunction "1_1") (pintype "passive"))
      (node (ref "R11") (pin "1") (pinfunction "1_1") (pintype "passive"))
      (node (ref "R12") (pin "1") (pinfunction "1_1") (pintype "passive"))
      (node (ref "R14") (pin "2") (pinfunction "2_2") (pintype "passive"))
      (node (ref "R15") (pin "2") (pinfunction "2_2") (pintype "passive"))
      (node (ref "R20") (pin "2") (pinfunction "2_2") (pintype "passive"))
      (node (ref "R5") (pin "2") (pinfunction "2_2") (pintype "passive"))
      (node (ref "T2") (pin "1") (pinfunction "D_1") (pintype "passive"))
      (node (ref "T5") (pin "2") (pinfunction "S_2") (pintype "passive"))
      (node (ref "X1") (pin "1") (pinfunction "1_1") (pintype "passive"))
    )
    (net (code "51") (name "unconnected-(BH1-+-Pad+1)") (class "Default")
      (node (ref "BH1") (pin "+1") (pinfunction "+_+1") (pintype "passive"))
    )
    (net (code "52") (name "unconnected-(IC1A-PA2{slash}CMU_CLK0#0{slash}TIM0_CC2#0,1-Pad3)") (class "Default")
      (node (ref "IC1") (pin "3") (pinfunction "PA2/CMU_CLK0#0/TIM0_CC2#0,1_3") (pintype "bidirectional"))
    )
    (net (code "53") (name "unconnected-(IC1A-PA6{slash}LEU1_RX#1-Pad7)") (class "Default")
      (node (ref "IC1") (pin "7") (pinfunction "PA6/LEU1_RX#1_7") (pintype "bidirectional"))
    )
    (net (code "54") (name "unconnected-(IC1A-PA9{slash}TIM2_CC1#0-Pad18)") (class "Default")
      (node (ref "IC1") (pin "18") (pinfunction "PA9/TIM2_CC1#0_18") (pintype "bidirectional"))
    )
    (net (code "55") (name "unconnected-(IC1A-PA10{slash}TIM2_CC2#0-Pad19)") (class "Default")
      (node (ref "IC1") (pin "19") (pinfunction "PA10/TIM2_CC2#0_19") (pintype "bidirectional"))
    )
    (net (code "56") (name "unconnected-(IC1B-PB11{slash}DAC0_OUT0{slash}OPAMP_OUT0{slash}LETIM0_OUT0#1-Pad21)") (class "Default")
      (node (ref "IC1") (pin "21") (pinfunction "PB11/DAC0_OUT0/OPAMP_OUT0/LETIM0_OUT0#1_21") (pintype "bidirectional"))
    )
    (net (code "57") (name "unconnected-(IC1B-PB12{slash}DAC0_OUT1{slash}OPAMP_OUT1{slash}LETIM0_OUT1#1-Pad22)") (class "Default")
      (node (ref "IC1") (pin "22") (pinfunction "PB12/DAC0_OUT1/OPAMP_OUT1/LETIM0_OUT1#1_22") (pintype "bidirectional"))
    )
    (net (code "58") (name "unconnected-(IC1C-PC0{slash}ACMP0_CH0{slash}PCNT0_S0IN#2{slash}US1_TX#0-Pad9)") (class "Default")
      (node (ref "IC1") (pin "9") (pinfunction "PC0/ACMP0_CH0/PCNT0_S0IN#2/US1_TX#0_9") (pintype "bidirectional"))
    )
    (net (code "59") (name "unconnected-(IC1C-PC1{slash}ACMP0_CH1{slash}PCNT0_S1IN#2{slash}US1_RX#0-Pad10)") (class "Default")
      (node (ref "IC1") (pin "10") (pinfunction "PC1/ACMP0_CH1/PCNT0_S1IN#2/US1_RX#0_10") (pintype "bidirectional"))
    )
    (net (code "60") (name "unconnected-(IC1C-PC2{slash}ACMP0_CH2{slash}US2_TX-Pad11)") (class "Default")
      (node (ref "IC1") (pin "11") (pinfunction "PC2/ACMP0_CH2/US2_TX_11") (pintype "bidirectional"))
    )
    (net (code "61") (name "unconnected-(IC1C-PC3{slash}ACMP0_CH3{slash}US2_RX-Pad12)") (class "Default")
      (node (ref "IC1") (pin "12") (pinfunction "PC3/ACMP0_CH3/US2_RX_12") (pintype "bidirectional"))
    )
    (net (code "62") (name "unconnected-(IC1C-PC4{slash}ACMP0_CH4{slash}LETIM0_OUT0#3{slash}PCNT1_S0IN{slash}US2_CLK-Pad13)") (class "Default")
      (node (ref "IC1") (pin "13") (pinfunction "PC4/ACMP0_CH4/LETIM0_OUT0#3/PCNT1_S0IN/US2_CLK_13") (pintype "bidirectional"))
    )
    (net (code "63") (name "unconnected-(IC1C-PC5{slash}ACMP0_CH5{slash}LETIM0_OUT1#3{slash}PCNT1_S1IN{slash}US2_CS-Pad14)") (class "Default")
      (node (ref "IC1") (pin "14") (pinfunction "PC5/ACMP0_CH5/LETIM0_OUT1#3/PCNT1_S1IN/US2_CS_14") (pintype "bidirectional"))
    )
    (net (code "64") (name "unconnected-(IC1C-PC6{slash}ACMP0_CH6{slash}I2C0_SDA#2{slash}LEU1_TX#0-Pad37)") (class "Default")
      (node (ref "IC1") (pin "37") (pinfunction "PC6/ACMP0_CH6/I2C0_SDA#2/LEU1_TX#0_37") (pintype "bidirectional"))
    )
    (net (code "65") (name "unconnected-(IC1C-PC7{slash}ACMP0_CH7{slash}I2C0_SCL#2{slash}LEU1_RX#0-Pad38)") (class "Default")
      (node (ref "IC1") (pin "38") (pinfunction "PC7/ACMP0_CH7/I2C0_SCL#2/LEU1_RX#0_38") (pintype "bidirectional"))
    )
    (net (code "66") (name "unconnected-(IC1C-PC8{slash}ACMP1_CH0{slash}TIM2_CC0#2{slash}US0_CS#2-Pad41)") (class "Default")
      (node (ref "IC1") (pin "41") (pinfunction "PC8/ACMP1_CH0/TIM2_CC0#2/US0_CS#2_41") (pintype "bidirectional"))
    )
    (net (code "67") (name "unconnected-(IC1C-PC9{slash}ACMP1_CH1{slash}TIM2_CC1#2{slash}US0_CLK#2-Pad42)") (class "Default")
      (node (ref "IC1") (pin "42") (pinfunction "PC9/ACMP1_CH1/TIM2_CC1#2/US0_CLK#2_42") (pintype "bidirectional"))
    )
    (net (code "68") (name "unconnected-(IC1C-PC10{slash}ACMP1_CH2{slash}TIM2_CC2#2{slash}US0_RX#2-Pad43)") (class "Default")
      (node (ref "IC1") (pin "43") (pinfunction "PC10/ACMP1_CH2/TIM2_CC2#2/US0_RX#2_43") (pintype "bidirectional"))
    )
    (net (code "69") (name "unconnected-(IC1C-PC11{slash}ACMP1_CH3{slash}US0_TX#2-Pad44)") (class "Default")
      (node (ref "IC1") (pin "44") (pinfunction "PC11/ACMP1_CH3/US0_TX#2_44") (pintype "bidirectional"))
    )
    (net (code "70") (name "unconnected-(IC1C-PC12{slash}ACMP1_CH4{slash}CMU_CLK0#1-Pad45)") (class "Default")
      (node (ref "IC1") (pin "45") (pinfunction "PC12/ACMP1_CH4/CMU_CLK0#1_45") (pintype "bidirectional"))
    )
    (net (code "71") (name "unconnected-(IC1C-PC13{slash}ACMP1_CH5{slash}PCNT0_S0IN#0{slash}TIM0_CDTI0#1,3{slash}TIM1_CC0#0-Pad46)") (class "Default")
      (node (ref "IC1") (pin "46") (pinfunction "PC13/ACMP1_CH5/PCNT0_S0IN#0/TIM0_CDTI0#1,3/TIM1_CC0#0_46") (pintype "bidirectional"))
    )
    (net (code "72") (name "unconnected-(IC1C-PC14{slash}ACMP1_CH6{slash}PCNT0_S1IN#0{slash}TIM0_CDTI1#1,3{slash}TIM1_CC1#0-Pad47)") (class "Default")
      (node (ref "IC1") (pin "47") (pinfunction "PC14/ACMP1_CH6/PCNT0_S1IN#0/TIM0_CDTI1#1,3/TIM1_CC1#0_47") (pintype "bidirectional"))
    )
    (net (code "73") (name "unconnected-(IC1C-PC15{slash}ACMP1_CH7{slash}DBG_SWO#1{slash}TIM0_CDTI2#1,3{slash}TIM1_CC2#0-Pad48)") (class "Default")
      (node (ref "IC1") (pin "48") (pinfunction "PC15/ACMP1_CH7/DBG_SWO#1/TIM0_CDTI2#1,3/TIM1_CC2#0_48") (pintype "bidirectional"))
    )
    (net (code "74") (name "unconnected-(IC1D-PD1{slash}ADC0_CH1{slash}PCNT2_S1IN#0{slash}TIM0_CC0#3{slash}US1_RX#1-Pad29)") (class "Default")
      (node (ref "IC1") (pin "29") (pinfunction "PD1/ADC0_CH1/PCNT2_S1IN#0/TIM0_CC0#3/US1_RX#1_29") (pintype "bidirectional"))
    )
    (net (code "75") (name "unconnected-(IC1D-PD2{slash}ADC0_CH2{slash}TIM0_CC1#3{slash}US1_CLK#1-Pad30)") (class "Default")
      (node (ref "IC1") (pin "30") (pinfunction "PD2/ADC0_CH2/TIM0_CC1#3/US1_CLK#1_30") (pintype "bidirectional"))
    )
    (net (code "76") (name "unconnected-(IC1D-PD3{slash}ADC0_CH3{slash}TIM0_CC2#3{slash}US1_CS#1-Pad31)") (class "Default")
      (node (ref "IC1") (pin "31") (pinfunction "PD3/ADC0_CH3/TIM0_CC2#3/US1_CS#1_31") (pintype "bidirectional"))
    )
    (net (code "77") (name "unconnected-(IC1D-PD6{slash}ADC0_CH6{slash}I2C0_SDA#1{slash}LETIM0_OUT0#0-Pad34)") (class "Default")
      (node (ref "IC1") (pin "34") (pinfunction "PD6/ADC0_CH6/I2C0_SDA#1/LETIM0_OUT0#0_34") (pintype "bidirectional"))
    )
    (net (code "78") (name "unconnected-(IC1D-PD7{slash}ADC0_CH7{slash}I2C0_SCL#1{slash}LETIM0_OUT1#0-Pad35)") (class "Default")
      (node (ref "IC1") (pin "35") (pinfunction "PD7/ADC0_CH7/I2C0_SCL#1/LETIM0_OUT1#0_35") (pintype "bidirectional"))
    )
    (net (code "79") (name "unconnected-(IC1D-PD8{slash}CMU_CLK1#1-Pad36)") (class "Default")
      (node (ref "IC1") (pin "36") (pinfunction "PD8/CMU_CLK1#1_36") (pintype "bidirectional"))
    )
    (net (code "80") (name "unconnected-(X1-Pad7)") (class "Default")
      (node (ref "X1") (pin "7") (pinfunction "7_7") (pintype "passive"))
    )
  )
)
